# rev1.net
KiCad netlist of a schematic drawn in EAGLE
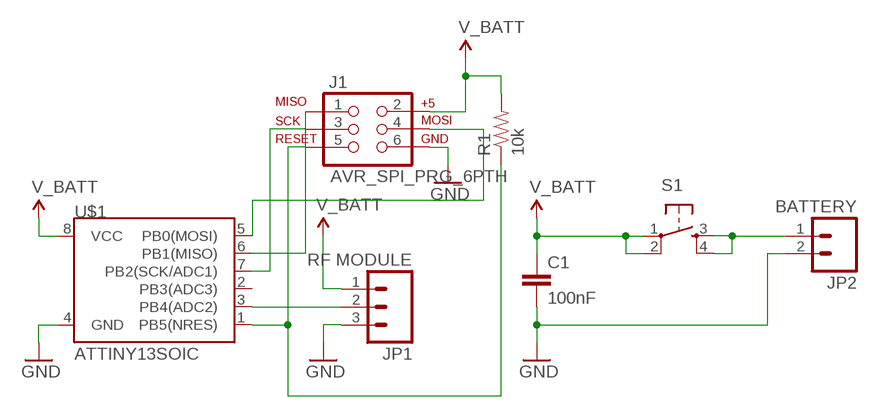
[diagram p0: schematic, sheet 1]

(export (version "E")
  (design (tool "Eeschema 10.0.6"))
  (components
    (comp (ref "C1")
      (value "100nF")
      (footprint "eagle-import:1206")
      (libsource (lib "eagle-import") (part "CAP1206"))
    )
    (comp (ref "J1")
      (value "AVR_SPI_PRG_6PTH")
      (footprint "eagle-import:2X3")
      (libsource (lib "eagle-import") (part "AVR_SPI_PRG_6PTH"))
    )
    (comp (ref "JP1")
      (value "RF MODULE")
      (footprint "eagle-import:1X03")
      (libsource (lib "eagle-import") (part "M03PTH"))
    )
    (comp (ref "JP2")
      (value "BATTERY")
      (footprint "eagle-import:1X02")
      (libsource (lib "eagle-import") (part "M02PTH"))
    )
    (comp (ref "R1")
      (value "10k")
      (footprint "eagle-import:1206")
      (libsource (lib "eagle-import") (part "RESISTOR1206"))
    )
    (comp (ref "S1")
      (value "TAC_SWITCHPTH")
      (footprint "eagle-import:TACTILE-PTH")
      (libsource (lib "eagle-import") (part "TAC_SWITCHPTH"))
    )
    (comp (ref "U$1")
      (value "ATTINY13SOIC")
      (footprint "eagle-import:SO08")
      (libsource (lib "eagle-import") (part "ATTINY13SOIC"))
    )
  )
  (nets
    (net (code "1") (name "GND") (class "Default")
      (node (ref "C1") (pin "2") (pinfunction "2_2") (pintype "passive"))
      (node (ref "J1") (pin "6") (pinfunction "6_6") (pintype "passive"))
      (node (ref "JP1") (pin "3") (pinfunction "3_3") (pintype "passive"))
      (node (ref "JP2") (pin "2") (pinfunction "2_2") (pintype "passive"))
      (node (ref "U$1") (pin "4") (pinfunction "GND_4") (pintype "bidirectional"))
    )
    (net (code "2") (name "Net-(JP2-Pad1)") (class "Default")
      (node (ref "JP2") (pin "1") (pinfunction "1_1") (pintype "passive"))
      (node (ref "S1") (pin "3") (pinfunction "3_3") (pintype "passive"))
      (node (ref "S1") (pin "4") (pinfunction "4_4") (pintype "passive"))
    )
    (net (code "3") (name "Net-(U$1-PB0(MOSI))") (class "Default")
      (node (ref "J1") (pin "4") (pinfunction "4_4") (pintype "passive"))
      (node (ref "U$1") (pin "5") (pinfunction "PB0(MOSI)_5") (pintype "bidirectional"))
    )
    (net (code "4") (name "Net-(U$1-PB1(MISO))") (class "Default")
      (node (ref "J1") (pin "1") (pinfunction "1_1") (pintype "passive"))
      (node (ref "U$1") (pin "6") (pinfunction "PB1(MISO)_6") (pintype "bidirectional"))
    )
    (net (code "5") (name "Net-(U$1-PB2(SCK{slash}ADC1))") (class "Default")
      (node (ref "J1") (pin "3") (pinfunction "3_3") (pintype "passive"))
      (node (ref "U$1") (pin "7") (pinfunction "PB2(SCK/ADC1)_7") (pintype "bidirectional"))
    )
    (net (code "6") (name "Net-(U$1-PB4(ADC2))") (class "Default")
      (node (ref "JP1") (pin "2") (pinfunction "2_2") (pintype "passive"))
      (node (ref "U$1") (pin "3") (pinfunction "PB4(ADC2)_3") (pintype "bidirectional"))
    )
    (net (code "7") (name "Net-(U$1-PB5(NRES))") (class "Default")
      (node (ref "J1") (pin "5") (pinfunction "5_5") (pintype "passive"))
      (node (ref "R1") (pin "1") (pinfunction "1_1") (pintype "passive"))
      (node (ref "U$1") (pin "1") (pinfunction "PB5(NRES)_1") (pintype "bidirectional"))
    )
    (net (code "8") (name "V_BATT") (class "Default")
      (node (ref "C1") (pin "1") (pinfunction "1_1") (pintype "passive"))
      (node (ref "J1") (pin "2") (pinfunction "2_2") (pintype "passive"))
      (node (ref "JP1") (pin "1") (pinfunction "1_1") (pintype "passive"))
      (node (ref "R1") (pin "2") (pinfunction "2_2") (pintype "passive"))
      (node (ref "S1") (pin "1") (pinfunction "1_1") (pintype "passive"))
      (node (ref "S1") (pin "2") (pinfunction "2_2") (pintype "passive"))
      (node (ref "U$1") (pin "8") (pinfunction "VCC_8") (pintype "bidirectional"))
    )
    (net (code "9") (name "unconnected-(U$1-PB3(ADC3)-Pad2)") (class "Default")
      (node (ref "U$1") (pin "2") (pinfunction "PB3(ADC3)_2") (pintype "bidirectional"))
    )
  )
)
